# ecgdesign4.net
KiCad netlist of a schematic drawn in EAGLE
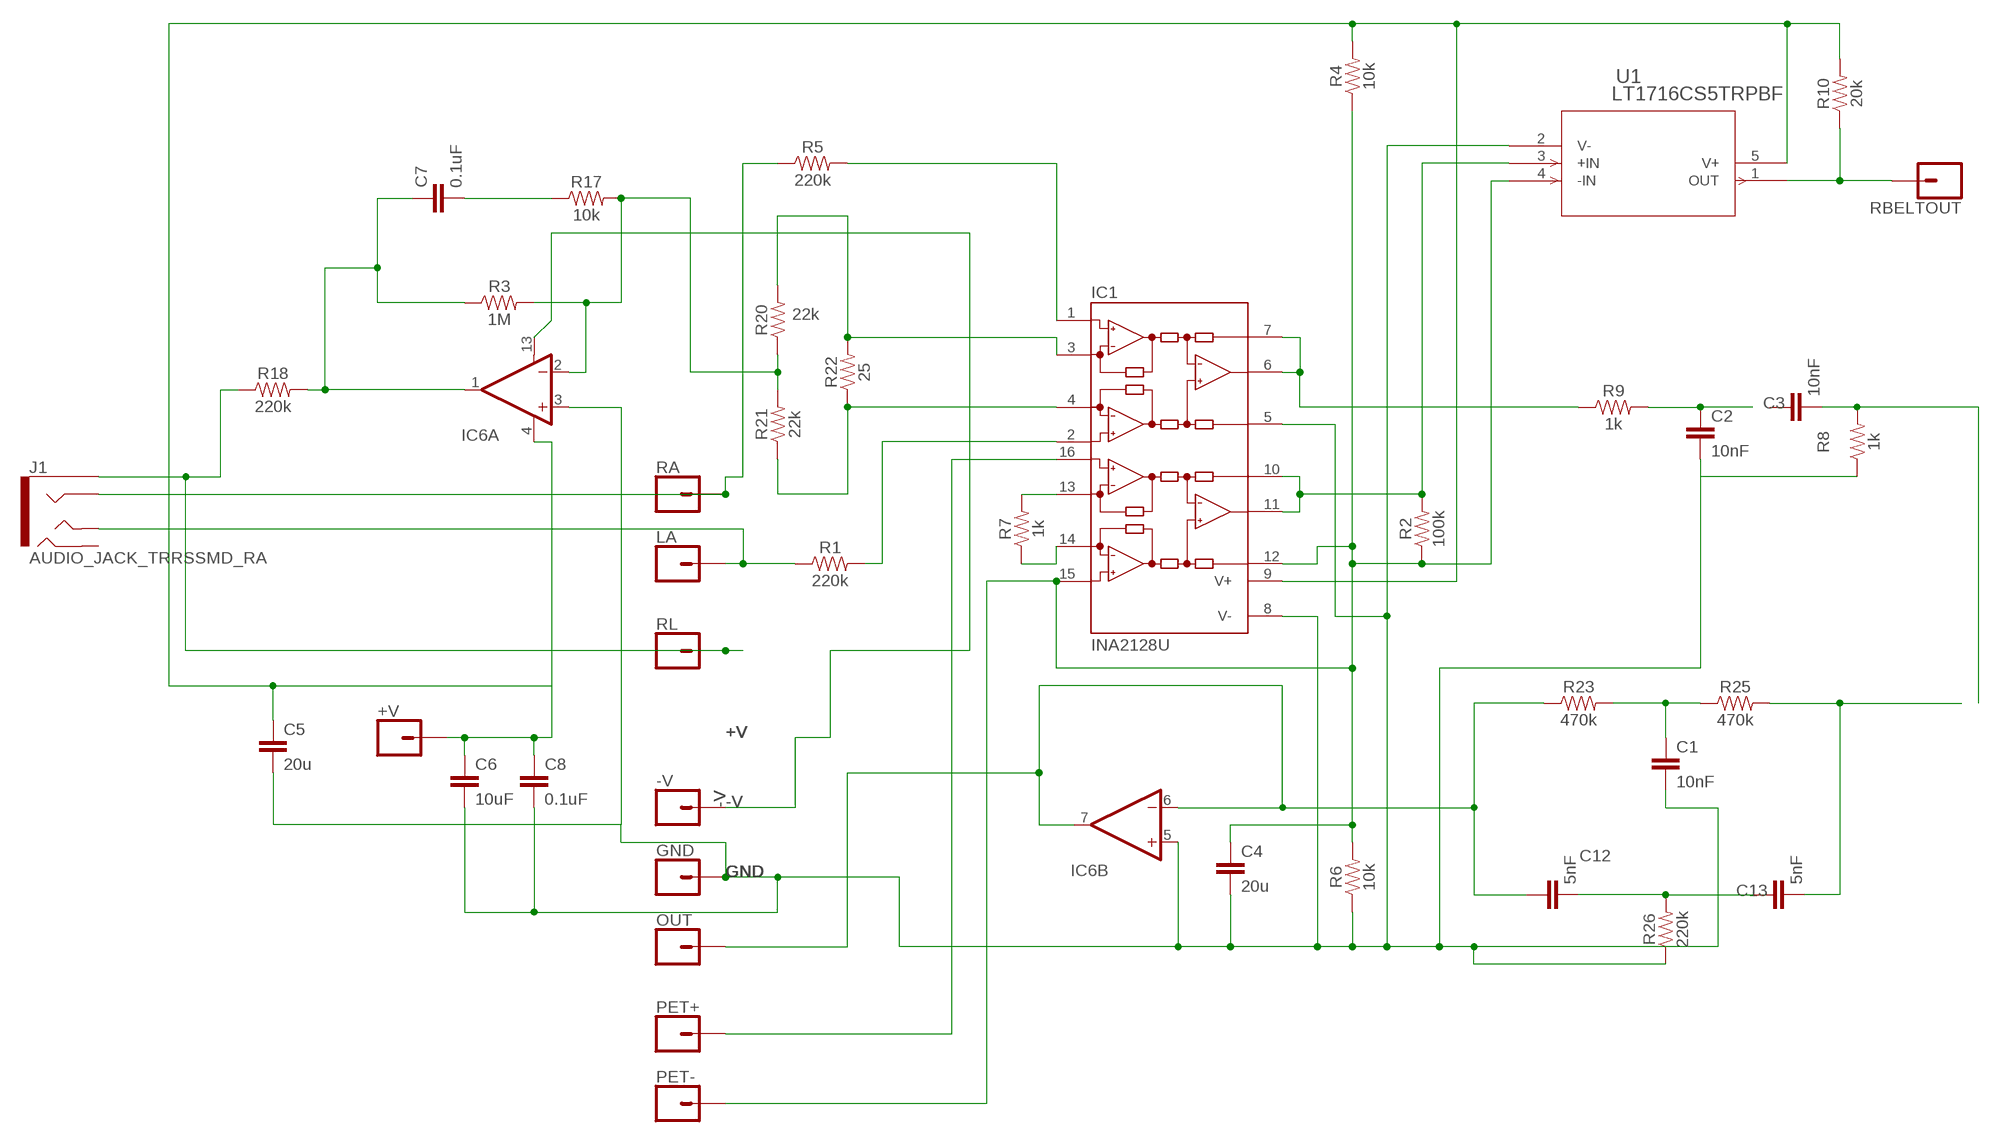
[diagram p0: schematic, sheet 1]

(export (version "E")
  (design (tool "Eeschema 10.0.6"))
  (components
    (comp (ref "+V")
      (value "CONN_01")
      (footprint "eagle-import:1X01")
      (libsource (lib "eagle-import") (part "CONN_01"))
    )
    (comp (ref "-V")
      (value "CONN_01")
      (footprint "eagle-import:1X01")
      (libsource (lib "eagle-import") (part "CONN_01"))
    )
    (comp (ref "C1")
      (value "10nF")
      (footprint "eagle-import:CAP-PTH-10MM")
      (libsource (lib "eagle-import") (part "10NF-PTH-10MM-10000V-1-%"))
    )
    (comp (ref "C2")
      (value "10nF")
      (footprint "eagle-import:CAP-PTH-10MM")
      (libsource (lib "eagle-import") (part "10NF-PTH-10MM-10000V-1-%"))
    )
    (comp (ref "C3")
      (value "10nF")
      (footprint "eagle-import:CAP-PTH-10MM")
      (libsource (lib "eagle-import") (part "10NF-PTH-10MM-10000V-1-%"))
    )
    (comp (ref "C4")
      (value "20u")
      (footprint "eagle-import:C37.5B20")
      (libsource (lib "eagle-import") (part "C37/20"))
    )
    (comp (ref "C5")
      (value "20u")
      (footprint "eagle-import:C37.5B20")
      (libsource (lib "eagle-import") (part "C37/20"))
    )
    (comp (ref "C6")
      (value "10uF")
      (footprint "eagle-import:CAP-PTH-10MM")
      (libsource (lib "eagle-import") (part "10NF-PTH-10MM-10000V-1-%"))
    )
    (comp (ref "C7")
      (value "0.1uF")
      (footprint "eagle-import:CAP-PTH-10MM")
      (libsource (lib "eagle-import") (part "10NF-PTH-10MM-10000V-1-%"))
    )
    (comp (ref "C8")
      (value "0.1uF")
      (footprint "eagle-import:CAP-PTH-10MM")
      (libsource (lib "eagle-import") (part "10NF-PTH-10MM-10000V-1-%"))
    )
    (comp (ref "C12")
      (value "5nF")
      (footprint "eagle-import:CAP-PTH-10MM")
      (libsource (lib "eagle-import") (part "10NF-PTH-10MM-10000V-1-%"))
    )
    (comp (ref "C13")
      (value "5nF")
      (footprint "eagle-import:CAP-PTH-10MM")
      (libsource (lib "eagle-import") (part "10NF-PTH-10MM-10000V-1-%"))
    )
    (comp (ref "GND")
      (value "CONN_01")
      (footprint "eagle-import:1X01")
      (libsource (lib "eagle-import") (part "CONN_01"))
    )
    (comp (ref "IC1")
      (value "INA2128U")
      (footprint "eagle-import:SO16-1")
      (fields (field (name "MF") "TEXAS INSTRUMENTS"))
      (libsource (lib "eagle-import") (part "INA2128U"))
    )
    (comp (ref "IC6")
      (value "OPA4336E")
      (footprint "eagle-import:SSOP16BU")
      (fields (field (name "MF") "TEXAS INSTRUMENTS") (field (name "MPN") "OPA4336EA/250"))
      (libsource (lib "eagle-import") (part "OPA4336E"))
    )
    (comp (ref "J1")
      (value "AUDIO_JACK_TRRSSMD_RA")
      (footprint "eagle-import:AUDIO_JACK_3.5MM_TRRS_SMD_RA")
      (libsource (lib "eagle-import") (part "AUDIO_JACK_TRRSSMD_RA"))
    )
    (comp (ref "LA")
      (value "CONN_01")
      (footprint "eagle-import:1X01")
      (libsource (lib "eagle-import") (part "CONN_01"))
    )
    (comp (ref "OUT")
      (value "CONN_01")
      (footprint "eagle-import:1X01")
      (libsource (lib "eagle-import") (part "CONN_01"))
    )
    (comp (ref "PET+")
      (value "CONN_01")
      (footprint "eagle-import:1X01")
      (libsource (lib "eagle-import") (part "CONN_01"))
    )
    (comp (ref "PET-")
      (value "CONN_01")
      (footprint "eagle-import:1X01")
      (libsource (lib "eagle-import") (part "CONN_01"))
    )
    (comp (ref "R1")
      (value "220k")
      (footprint "eagle-import:AXIAL-0.3")
      (libsource (lib "eagle-import") (part "10KOHM-HORIZ-1/4W-1%"))
    )
    (comp (ref "R2")
      (value "100k")
      (footprint "eagle-import:AXIAL-0.3")
      (libsource (lib "eagle-import") (part "10KOHM-HORIZ-1/4W-1%"))
    )
    (comp (ref "R3")
      (value "1M")
      (footprint "eagle-import:AXIAL-0.3")
      (libsource (lib "eagle-import") (part "10KOHM-HORIZ-1/4W-1%"))
    )
    (comp (ref "R4")
      (value "10k")
      (footprint "eagle-import:AXIAL-0.3")
      (libsource (lib "eagle-import") (part "10KOHM-HORIZ-1/4W-1%"))
    )
    (comp (ref "R5")
      (value "220k")
      (footprint "eagle-import:AXIAL-0.3")
      (libsource (lib "eagle-import") (part "10KOHM-HORIZ-1/4W-1%"))
    )
    (comp (ref "R6")
      (value "10k")
      (footprint "eagle-import:AXIAL-0.3")
      (libsource (lib "eagle-import") (part "10KOHM-HORIZ-1/4W-1%"))
    )
    (comp (ref "R7")
      (value "1k")
      (footprint "eagle-import:AXIAL-0.3")
      (libsource (lib "eagle-import") (part "10KOHM-HORIZ-1/4W-1%"))
    )
    (comp (ref "R8")
      (value "1k")
      (footprint "eagle-import:AXIAL-0.3")
      (libsource (lib "eagle-import") (part "1KOHM-HORIZ-1/4W-1%"))
    )
    (comp (ref "R9")
      (value "1k")
      (footprint "eagle-import:AXIAL-0.3")
      (libsource (lib "eagle-import") (part "1KOHM-HORIZ-1/4W-1%"))
    )
    (comp (ref "R10")
      (value "20k")
      (footprint "eagle-import:AXIAL-0.3")
      (libsource (lib "eagle-import") (part "10KOHM-HORIZ-1/4W-1%"))
    )
    (comp (ref "R17")
      (value "10k")
      (footprint "eagle-import:AXIAL-0.3")
      (libsource (lib "eagle-import") (part "1KOHM-HORIZ-1/4W-5%"))
    )
    (comp (ref "R18")
      (value "220k")
      (footprint "eagle-import:AXIAL-0.3")
      (libsource (lib "eagle-import") (part "1KOHM-HORIZ-1/4W-5%"))
    )
    (comp (ref "R20")
      (value "22k")
      (footprint "eagle-import:AXIAL-0.3")
      (libsource (lib "eagle-import") (part "1KOHM-HORIZ-1/4W-5%"))
    )
    (comp (ref "R21")
      (value "22k")
      (footprint "eagle-import:AXIAL-0.3")
      (libsource (lib "eagle-import") (part "1KOHM-HORIZ-1/4W-5%"))
    )
    (comp (ref "R22")
      (value "25")
      (footprint "eagle-import:AXIAL-0.3")
      (libsource (lib "eagle-import") (part "1KOHM-HORIZ-1/4W-5%"))
    )
    (comp (ref "R23")
      (value "470k")
      (footprint "eagle-import:AXIAL-0.3")
      (libsource (lib "eagle-import") (part "1KOHM-HORIZ-1/4W-5%"))
    )
    (comp (ref "R25")
      (value "470k")
      (footprint "eagle-import:AXIAL-0.3")
      (libsource (lib "eagle-import") (part "1KOHM-HORIZ-1/4W-5%"))
    )
    (comp (ref "R26")
      (value "220k")
      (footprint "eagle-import:AXIAL-0.3")
      (libsource (lib "eagle-import") (part "1KOHM-HORIZ-1/4W-5%"))
    )
    (comp (ref "RA")
      (value "CONN_01")
      (footprint "eagle-import:1X01")
      (libsource (lib "eagle-import") (part "CONN_01"))
    )
    (comp (ref "RBELTOUT")
      (value "CONN_01")
      (footprint "eagle-import:1X01")
      (libsource (lib "eagle-import") (part "CONN_01"))
    )
    (comp (ref "RL")
      (value "CONN_01")
      (footprint "eagle-import:1X01")
      (libsource (lib "eagle-import") (part "CONN_01"))
    )
    (comp (ref "U1")
      (value "LT1716CS5TRPBF")
      (footprint "eagle-import:SOT-5_S")
      (fields
        (field (name "DIGI-KEY_PART_NUMBER") "LT1716CS5#TRPBFCT-ND")
        (field (name "MF") "Linear Technology")
        (field (name "MP") "LT1716CS5#TRPBF")
      )
      (libsource (lib "eagle-import") (part "LT1716CS5TRPBF"))
    )
  )
  (nets
    (net (code "1") (name "/+V") (class "Default")
      (node (ref "+V") (pin "1") (pinfunction "1_1") (pintype "passive"))
      (node (ref "C5") (pin "1") (pinfunction "1_1") (pintype "passive"))
      (node (ref "C6") (pin "1") (pinfunction "1_1") (pintype "passive"))
      (node (ref "C8") (pin "1") (pinfunction "1_1") (pintype "passive"))
      (node (ref "IC1") (pin "9") (pinfunction "V+_9") (pintype "power_in"))
      (node (ref "IC6") (pin "4") (pinfunction "V+_4") (pintype "power_in"))
      (node (ref "R10") (pin "P$2") (pinfunction "2_P$2") (pintype "passive"))
      (node (ref "R4") (pin "P$2") (pinfunction "2_P$2") (pintype "passive"))
      (node (ref "U1") (pin "5") (pinfunction "V+_5") (pintype "power_in"))
    )
    (net (code "2") (name "/-V") (class "Default")
      (node (ref "-V") (pin "1") (pinfunction "1_1") (pintype "passive"))
      (node (ref "IC6") (pin "13") (pinfunction "V-_13") (pintype "power_in"))
    )
    (net (code "3") (name "/GND") (class "Default")
      (node (ref "C1") (pin "2") (pinfunction "2_2") (pintype "passive"))
      (node (ref "C2") (pin "2") (pinfunction "2_2") (pintype "passive"))
      (node (ref "C4") (pin "2") (pinfunction "2_2") (pintype "passive"))
      (node (ref "C5") (pin "2") (pinfunction "2_2") (pintype "passive"))
      (node (ref "C6") (pin "2") (pinfunction "2_2") (pintype "passive"))
      (node (ref "C8") (pin "2") (pinfunction "2_2") (pintype "passive"))
      (node (ref "GND") (pin "1") (pinfunction "1_1") (pintype "passive"))
      (node (ref "IC1") (pin "5") (pinfunction "REFA_5") (pintype "input"))
      (node (ref "IC1") (pin "8") (pinfunction "V-_8") (pintype "power_in"))
      (node (ref "IC6") (pin "3") (pinfunction "+IN_3") (pintype "input"))
      (node (ref "IC6") (pin "5") (pinfunction "+IN_5") (pintype "input"))
      (node (ref "R26") (pin "P$1") (pinfunction "1_P$1") (pintype "passive"))
      (node (ref "R6") (pin "P$1") (pinfunction "1_P$1") (pintype "passive"))
      (node (ref "R8") (pin "P$1") (pinfunction "1_P$1") (pintype "passive"))
      (node (ref "U1") (pin "2") (pinfunction "V-_2") (pintype "power_in"))
    )
    (net (code "4") (name "Net-(IC1-INA+)") (class "Default")
      (node (ref "IC1") (pin "2") (pinfunction "INA+_2") (pintype "input"))
      (node (ref "R1") (pin "P$2") (pinfunction "2_P$2") (pintype "passive"))
    )
    (net (code "5") (name "Net-(IC1-INA-)") (class "Default")
      (node (ref "IC1") (pin "1") (pinfunction "INA-_1") (pintype "input"))
      (node (ref "R5") (pin "P$2") (pinfunction "2_P$2") (pintype "passive"))
    )
    (net (code "6") (name "Net-(IC1-INB+)") (class "Default")
      (node (ref "C4") (pin "1") (pinfunction "1_1") (pintype "passive"))
      (node (ref "IC1") (pin "12") (pinfunction "REFB_12") (pintype "input"))
      (node (ref "IC1") (pin "15") (pinfunction "INB+_15") (pintype "input"))
      (node (ref "PET-") (pin "1") (pinfunction "1_1") (pintype "passive"))
      (node (ref "R2") (pin "P$1") (pinfunction "1_P$1") (pintype "passive"))
      (node (ref "R4") (pin "P$1") (pinfunction "1_P$1") (pintype "passive"))
      (node (ref "R6") (pin "P$2") (pinfunction "2_P$2") (pintype "passive"))
      (node (ref "U1") (pin "4") (pinfunction "-IN_4") (pintype "input"))
    )
    (net (code "7") (name "Net-(IC1-INB-)") (class "Default")
      (node (ref "IC1") (pin "16") (pinfunction "INB-_16") (pintype "input"))
      (node (ref "PET+") (pin "1") (pinfunction "1_1") (pintype "passive"))
    )
    (net (code "8") (name "Net-(IC1-SENSEA)") (class "Default")
      (node (ref "IC1") (pin "6") (pinfunction "VOA_6") (pintype "output"))
      (node (ref "IC1") (pin "7") (pinfunction "SENSEA_7") (pintype "input"))
      (node (ref "R9") (pin "P$1") (pinfunction "1_P$1") (pintype "passive"))
    )
    (net (code "9") (name "Net-(IC1-SENSEB)") (class "Default")
      (node (ref "IC1") (pin "10") (pinfunction "SENSEB_10") (pintype "input"))
      (node (ref "IC1") (pin "11") (pinfunction "VOB_11") (pintype "output"))
      (node (ref "R2") (pin "P$2") (pinfunction "2_P$2") (pintype "passive"))
      (node (ref "U1") (pin "3") (pinfunction "+IN_3") (pintype "input"))
    )
    (net (code "10") (name "Net-(IC6A--IN)") (class "Default")
      (node (ref "IC6") (pin "2") (pinfunction "-IN_2") (pintype "input"))
      (node (ref "R17") (pin "P$2") (pinfunction "2_P$2") (pintype "passive"))
      (node (ref "R20") (pin "P$1") (pinfunction "1_P$1") (pintype "passive"))
      (node (ref "R21") (pin "P$2") (pinfunction "2_P$2") (pintype "passive"))
      (node (ref "R3") (pin "P$2") (pinfunction "2_P$2") (pintype "passive"))
    )
    (net (code "11") (name "Net-(IC6A-OUT)") (class "Default")
      (node (ref "C7") (pin "1") (pinfunction "1_1") (pintype "passive"))
      (node (ref "IC6") (pin "1") (pinfunction "OUT_1") (pintype "output"))
      (node (ref "R18") (pin "P$2") (pinfunction "2_P$2") (pintype "passive"))
      (node (ref "R3") (pin "P$1") (pinfunction "1_P$1") (pintype "passive"))
    )
    (net (code "12") (name "Net-(IC6B--IN)") (class "Default")
      (node (ref "C12") (pin "1") (pinfunction "1_1") (pintype "passive"))
      (node (ref "IC6") (pin "6") (pinfunction "-IN_6") (pintype "input"))
      (node (ref "IC6") (pin "7") (pinfunction "OUT_7") (pintype "output"))
      (node (ref "OUT") (pin "1") (pinfunction "1_1") (pintype "passive"))
      (node (ref "R23") (pin "P$1") (pinfunction "1_P$1") (pintype "passive"))
    )
    (net (code "13") (name "Net-(R1-1)") (class "Default")
      (node (ref "J1") (pin "TIP") (pinfunction "TIP_TIP") (pintype "bidirectional"))
      (node (ref "LA") (pin "1") (pinfunction "1_1") (pintype "passive"))
      (node (ref "R1") (pin "P$1") (pinfunction "1_P$1") (pintype "passive"))
    )
    (net (code "14") (name "Net-(R5-1)") (class "Default")
      (node (ref "J1") (pin "RING1") (pinfunction "RING1_RING1") (pintype "bidirectional"))
      (node (ref "R5") (pin "P$1") (pinfunction "1_P$1") (pintype "passive"))
      (node (ref "RA") (pin "1") (pinfunction "1_1") (pintype "passive"))
    )
    (net (code "15") (name "Net-(R7-1)") (class "Default")
      (node (ref "IC1") (pin "14") (pinfunction "RGB_14") (pintype "passive"))
      (node (ref "R7") (pin "P$1") (pinfunction "1_P$1") (pintype "passive"))
    )
    (net (code "16") (name "Net-(R7-2)") (class "Default")
      (node (ref "IC1") (pin "13") (pinfunction "RGB_13") (pintype "passive"))
      (node (ref "R7") (pin "P$2") (pinfunction "2_P$2") (pintype "passive"))
    )
    (net (code "17") (name "Net-(R8-2)") (class "Default")
      (node (ref "C3") (pin "2") (pinfunction "2_2") (pintype "passive"))
      (node (ref "R8") (pin "P$2") (pinfunction "2_P$2") (pintype "passive"))
    )
    (net (code "18") (name "Net-(R9-2)") (class "Default")
      (node (ref "C2") (pin "1") (pinfunction "1_1") (pintype "passive"))
      (node (ref "R9") (pin "P$2") (pinfunction "2_P$2") (pintype "passive"))
    )
    (net (code "19") (name "Net-(R10-1)") (class "Default")
      (node (ref "R10") (pin "P$1") (pinfunction "1_P$1") (pintype "passive"))
      (node (ref "RBELTOUT") (pin "1") (pinfunction "1_1") (pintype "passive"))
      (node (ref "U1") (pin "1") (pinfunction "OUT_1") (pintype "output"))
    )
    (net (code "20") (name "Net-(R17-1)") (class "Default")
      (node (ref "C7") (pin "2") (pinfunction "2_2") (pintype "passive"))
      (node (ref "R17") (pin "P$1") (pinfunction "1_P$1") (pintype "passive"))
    )
    (net (code "21") (name "Net-(R18-1)") (class "Default")
      (node (ref "J1") (pin "EARTH") (pinfunction "EARTH_EARTH") (pintype "bidirectional"))
      (node (ref "R18") (pin "P$1") (pinfunction "1_P$1") (pintype "passive"))
      (node (ref "RL") (pin "1") (pinfunction "1_1") (pintype "passive"))
    )
    (net (code "22") (name "Net-(R20-2)") (class "Default")
      (node (ref "IC1") (pin "3") (pinfunction "RGA_3") (pintype "passive"))
      (node (ref "R20") (pin "P$2") (pinfunction "2_P$2") (pintype "passive"))
      (node (ref "R22") (pin "P$2") (pinfunction "2_P$2") (pintype "passive"))
    )
    (net (code "23") (name "Net-(R21-1)") (class "Default")
      (node (ref "IC1") (pin "4") (pinfunction "RGA_4") (pintype "passive"))
      (node (ref "R21") (pin "P$1") (pinfunction "1_P$1") (pintype "passive"))
      (node (ref "R22") (pin "P$1") (pinfunction "1_P$1") (pintype "passive"))
    )
    (net (code "24") (name "Net-(R23-2)") (class "Default")
      (node (ref "C1") (pin "1") (pinfunction "1_1") (pintype "passive"))
      (node (ref "R23") (pin "P$2") (pinfunction "2_P$2") (pintype "passive"))
      (node (ref "R25") (pin "P$1") (pinfunction "1_P$1") (pintype "passive"))
    )
    (net (code "25") (name "Net-(R25-2)") (class "Default")
      (node (ref "C13") (pin "2") (pinfunction "2_2") (pintype "passive"))
      (node (ref "R25") (pin "P$2") (pinfunction "2_P$2") (pintype "passive"))
    )
    (net (code "26") (name "Net-(R26-2)") (class "Default")
      (node (ref "C12") (pin "2") (pinfunction "2_2") (pintype "passive"))
      (node (ref "C13") (pin "1") (pinfunction "1_1") (pintype "passive"))
      (node (ref "R26") (pin "P$2") (pinfunction "2_P$2") (pintype "passive"))
    )
    (net (code "27") (name "unconnected-(C3-Pad1)") (class "Default")
      (node (ref "C3") (pin "1") (pinfunction "1_1") (pintype "passive"))
    )
    (net (code "28") (name "unconnected-(J1-PadRING2)") (class "Default")
      (node (ref "J1") (pin "RING2") (pinfunction "RING2_RING2") (pintype "bidirectional"))
    )
  )
)
